# Adafruit_TPS61023.net
KiCad netlist of a schematic drawn in EAGLE
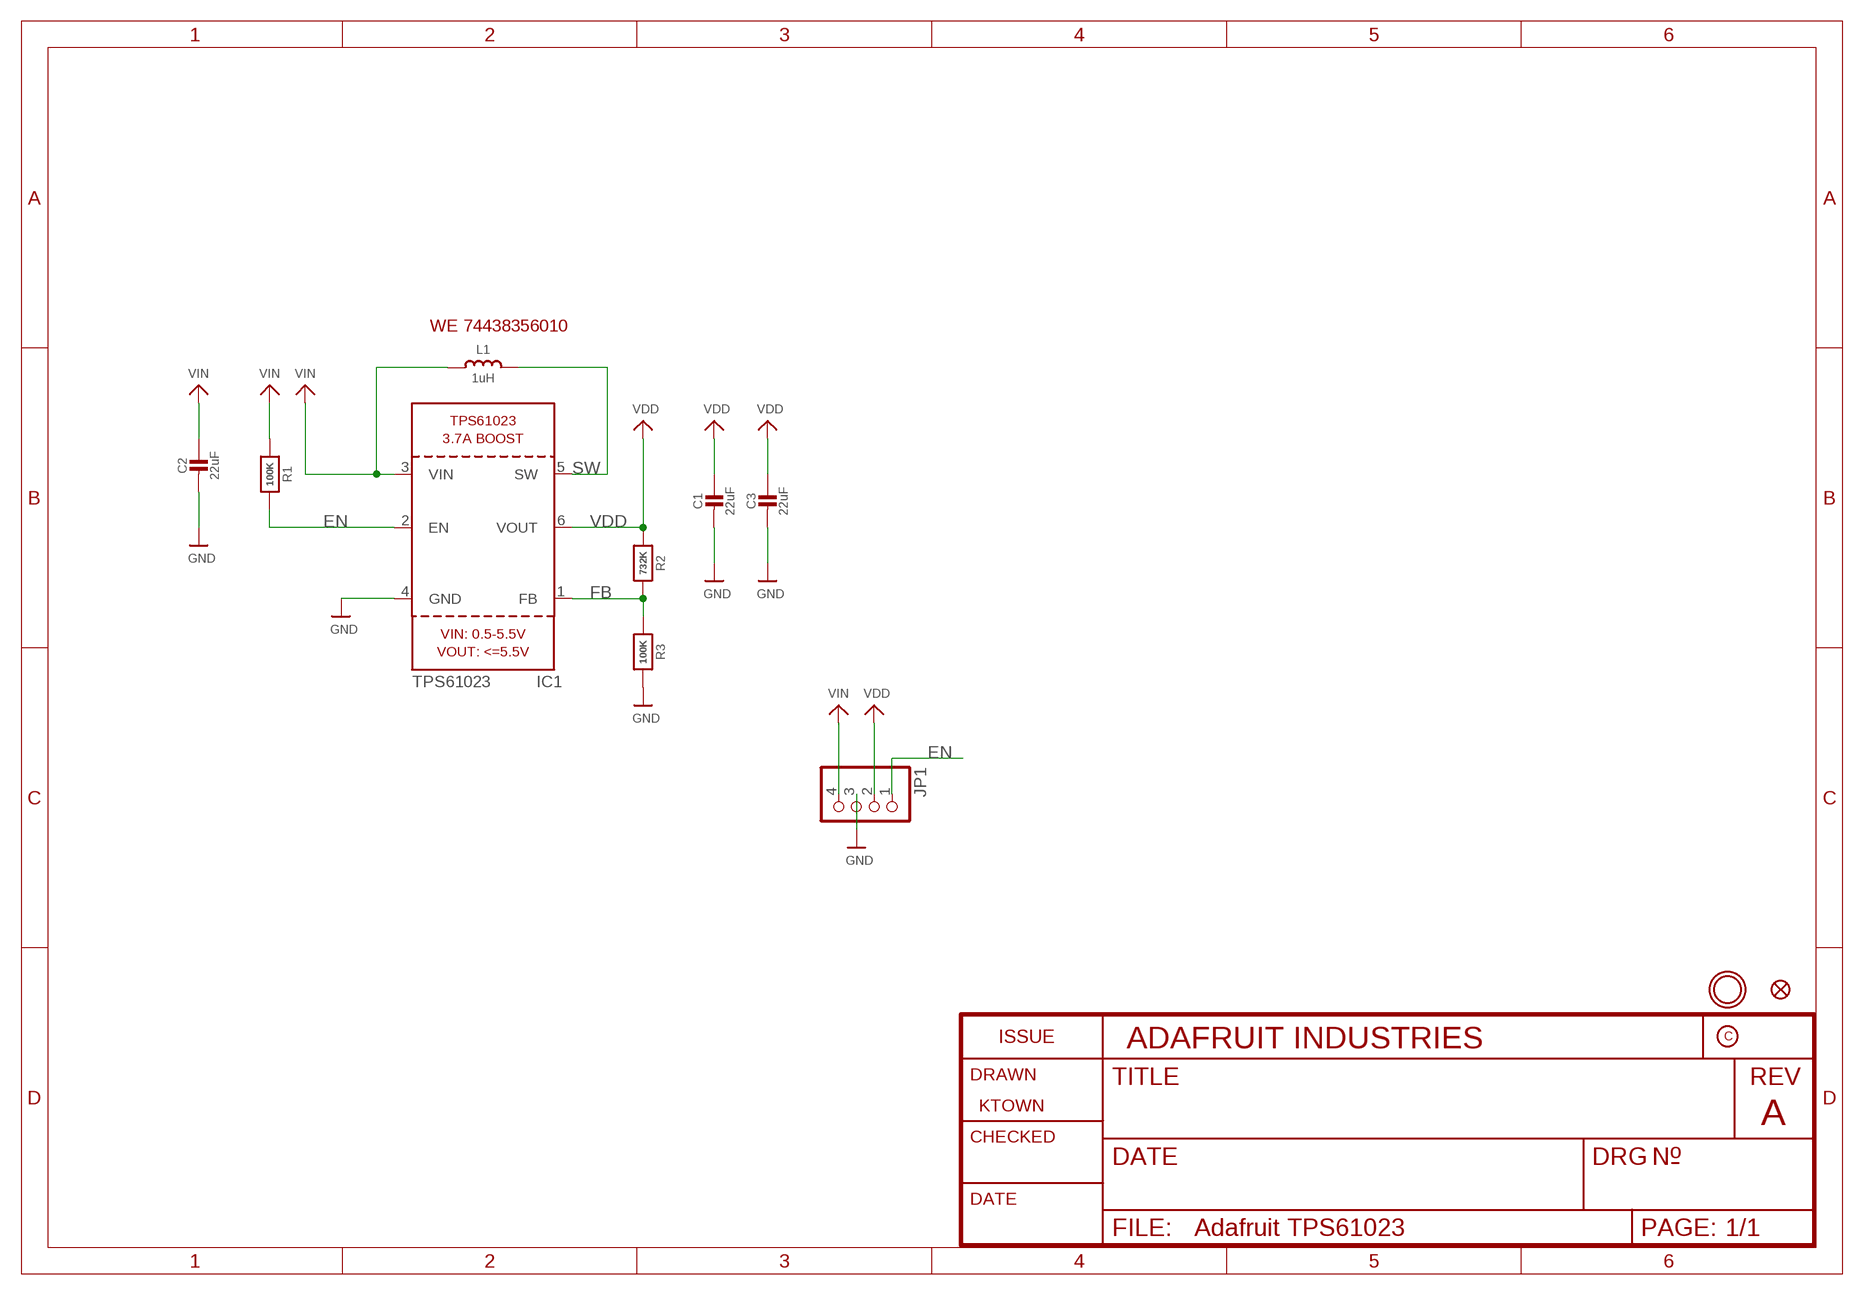
[diagram p0: schematic, sheet 1]

(export (version "E")
  (design (tool "Eeschema 10.0.6"))
  (components
    (comp (ref "C1")
      (value "22uF")
      (footprint "eagle-import:0805-NO")
      (libsource (lib "eagle-import") (part "CAP_CERAMIC0805-NOOUTLINE"))
    )
    (comp (ref "C2")
      (value "22uF")
      (footprint "eagle-import:0805-NO")
      (libsource (lib "eagle-import") (part "CAP_CERAMIC0805-NOOUTLINE"))
    )
    (comp (ref "C3")
      (value "22uF")
      (footprint "eagle-import:0805-NO")
      (libsource (lib "eagle-import") (part "CAP_CERAMIC0805-NOOUTLINE"))
    )
    (comp (ref "FID1")
      (value "FIDUCIAL_1MM")
      (footprint "eagle-import:FIDUCIAL_1MM")
      (libsource (lib "eagle-import") (part "FIDUCIAL_1MM"))
    )
    (comp (ref "IC1")
      (value "TPS61023")
      (footprint "eagle-import:SOT563")
      (libsource (lib "eagle-import") (part "TPS61023"))
    )
    (comp (ref "JP1")
      (value "HEADER-1X4ROUND")
      (footprint "eagle-import:1X04_ROUND")
      (libsource (lib "eagle-import") (part "HEADER-1X4ROUND"))
    )
    (comp (ref "L1")
      (value "1uH")
      (footprint "eagle-import:INDUCTOR_5X5MM_TDK_VLC5045")
      (libsource (lib "eagle-import") (part "INDUCTORTDK_VLC5045"))
    )
    (comp (ref "R1")
      (value "100K")
      (footprint "eagle-import:0603-NO")
      (libsource (lib "eagle-import") (part "RESISTOR_0603_NOOUT"))
    )
    (comp (ref "R2")
      (value "732K")
      (footprint "eagle-import:0603-NO")
      (libsource (lib "eagle-import") (part "RESISTOR_0603_NOOUT"))
    )
    (comp (ref "R3")
      (value "100K")
      (footprint "eagle-import:0603-NO")
      (libsource (lib "eagle-import") (part "RESISTOR_0603_NOOUT"))
    )
    (comp (ref "U$9")
      (value "MOUNTINGHOLE2.5")
      (footprint "eagle-import:MOUNTINGHOLE_2.5_PLATED")
      (libsource (lib "eagle-import") (part "MOUNTINGHOLE2.5"))
    )
  )
  (nets
    (net (code "1") (name "/EN") (class "Default")
      (node (ref "IC1") (pin "2") (pinfunction "EN_2") (pintype "input"))
      (node (ref "JP1") (pin "1") (pinfunction "1_1") (pintype "passive"))
      (node (ref "R1") (pin "2") (pinfunction "2_2") (pintype "passive"))
    )
    (net (code "2") (name "/FB") (class "Default")
      (node (ref "IC1") (pin "1") (pinfunction "FB_1") (pintype "input"))
      (node (ref "R2") (pin "2") (pinfunction "2_2") (pintype "passive"))
      (node (ref "R3") (pin "1") (pinfunction "1_1") (pintype "passive"))
    )
    (net (code "3") (name "/SW") (class "Default")
      (node (ref "IC1") (pin "5") (pinfunction "SW_5") (pintype "input"))
      (node (ref "L1") (pin "P$2") (pinfunction "2_P$2") (pintype "passive"))
    )
    (net (code "4") (name "GND") (class "Default")
      (node (ref "C1") (pin "2") (pinfunction "2_2") (pintype "passive"))
      (node (ref "C2") (pin "2") (pinfunction "2_2") (pintype "passive"))
      (node (ref "C3") (pin "2") (pinfunction "2_2") (pintype "passive"))
      (node (ref "IC1") (pin "4") (pinfunction "GND_4") (pintype "power_in"))
      (node (ref "JP1") (pin "3") (pinfunction "3_3") (pintype "passive"))
      (node (ref "R3") (pin "2") (pinfunction "2_2") (pintype "passive"))
    )
    (net (code "5") (name "VDD") (class "Default")
      (node (ref "C1") (pin "1") (pinfunction "1_1") (pintype "passive"))
      (node (ref "C3") (pin "1") (pinfunction "1_1") (pintype "passive"))
      (node (ref "IC1") (pin "6") (pinfunction "VOUT_6") (pintype "power_in"))
      (node (ref "JP1") (pin "2") (pinfunction "2_2") (pintype "passive"))
      (node (ref "R2") (pin "1") (pinfunction "1_1") (pintype "passive"))
    )
    (net (code "6") (name "VIN") (class "Default")
      (node (ref "C2") (pin "1") (pinfunction "1_1") (pintype "passive"))
      (node (ref "IC1") (pin "3") (pinfunction "VIN_3") (pintype "power_in"))
      (node (ref "JP1") (pin "4") (pinfunction "4_4") (pintype "passive"))
      (node (ref "L1") (pin "P$1") (pinfunction "1_P$1") (pintype "passive"))
      (node (ref "R1") (pin "1") (pinfunction "1_1") (pintype "passive"))
    )
  )
)
